# design.net
KiCad netlist of a schematic drawn in Altium Designer
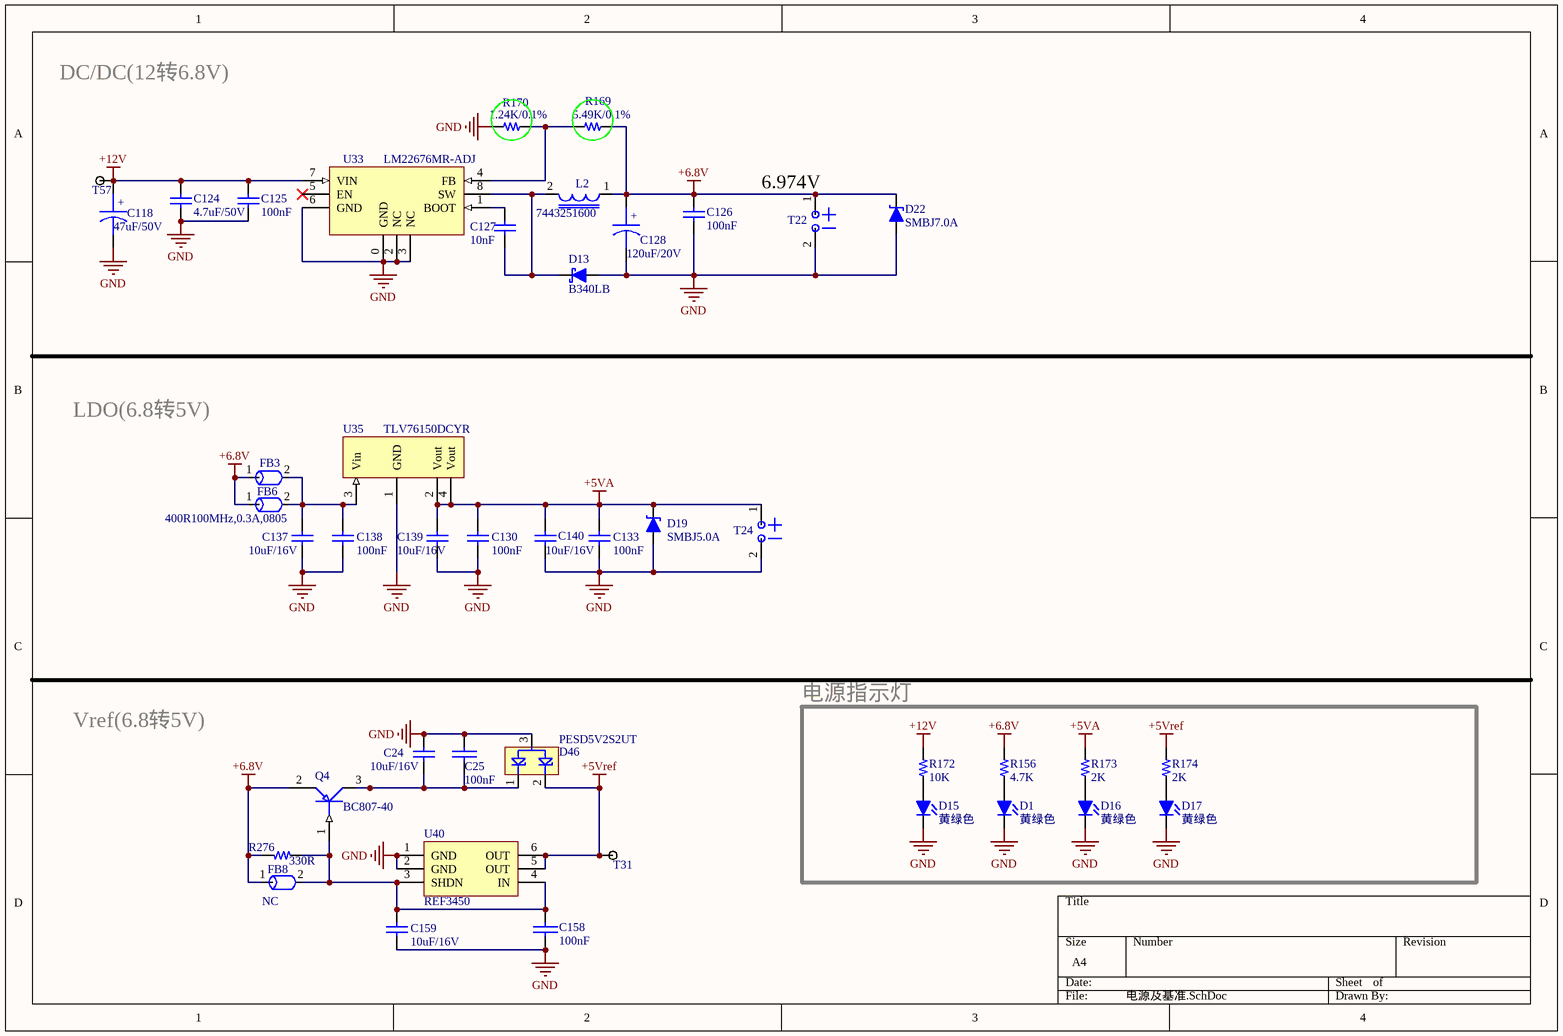
[diagram p0: 电源及基准.SchDoc]

(export (version "E")
  (design (tool "Eeschema 10.0.6"))
  (components
    (comp (ref "C24")
      (value "10uF/16V")
      (footprint "C-0805")
      (description "贴片瓷介电容100nF±5%,0805")
      (libsource (lib "电容") (part "100nF_1"))
    )
    (comp (ref "C25")
      (value "100nF")
      (footprint "C-0603")
      (description "Capacitor")
      (libsource (lib "*") (part "CAP"))
    )
    (comp (ref "C118")
      (value "47uF/50V")
      (footprint "CAP-SMD-φ6.3")
      (description "EEEFT1H470AP")
      (libsource (lib "电容") (part "10uF/16V贴片铝电解"))
    )
    (comp (ref "C124")
      (value "4.7uF/50V")
      (footprint "C-1210")
      (description "贴片瓷介电容100nF±5%,0805")
      (libsource (lib "电容") (part "100nF_1"))
    )
    (comp (ref "C125")
      (value "100nF")
      (footprint "C-0603")
      (description "贴片瓷介电容100nF±5%,0805")
      (libsource (lib "电容") (part "100nF_1"))
    )
    (comp (ref "C126")
      (value "100nF")
      (footprint "C-0603")
      (description "贴片瓷介电容100nF±5%,0805")
      (libsource (lib "电容") (part "100nF_1"))
    )
    (comp (ref "C127")
      (value "10nF")
      (footprint "C-0603")
      (description "贴片瓷介电容10nF±10%,0805")
      (libsource (lib "电容") (part "10nF_1"))
    )
    (comp (ref "C128")
      (value "120uF/20V")
      (footprint "CAP-SMD-φ6.3")
      (libsource (lib "电容") (part "100uF/25V贴片铝电解"))
    )
    (comp (ref "C130")
      (value "100nF")
      (footprint "C-0603")
      (description "贴片瓷介电容100nF±5%,0805")
      (libsource (lib "电容") (part "100nF_1"))
    )
    (comp (ref "C133")
      (value "100nF")
      (footprint "C-0603")
      (description "贴片瓷介电容100nF±5%,0805")
      (libsource (lib "电容") (part "100nF_1"))
    )
    (comp (ref "C137") (value "10uF/16V") (footprint "C-0805") (libsource (lib "Device") (part "C-1210")))
    (comp (ref "C138")
      (value "100nF")
      (footprint "C-0603")
      (description "贴片瓷介电容100nF±5%,0805")
      (libsource (lib "电容") (part "100nF_1"))
    )
    (comp (ref "C139") (value "10uF/16V") (footprint "C-0805") (libsource (lib "Device") (part "C-1210")))
    (comp (ref "C140") (value "10uF/16V") (footprint "C-0805") (libsource (lib "Device") (part "C-1210")))
    (comp (ref "C158")
      (value "100nF")
      (footprint "C-0603")
      (description "Capacitor")
      (libsource (lib "*") (part "CAP"))
    )
    (comp (ref "C159")
      (value "10uF/16V")
      (footprint "C-0805")
      (description "贴片瓷介电容100nF±5%,0805")
      (libsource (lib "电容") (part "100nF_1"))
    )
    (comp (ref "D1") (value "黄绿色") (footprint "LED-0805") (libsource (lib "Device") (part "LED-0805")))
    (comp (ref "D13")
      (value "B340LB")
      (footprint "DO-214AA/SMB")
      (libsource (lib "Device") (part "Diode-肖特基-214AA  (SMB)"))
    )
    (comp (ref "D15") (value "黄绿色") (footprint "LED-0805") (libsource (lib "Device") (part "LED-0805")))
    (comp (ref "D16") (value "黄绿色") (footprint "LED-0805") (libsource (lib "Device") (part "LED-0805")))
    (comp (ref "D17") (value "黄绿色") (footprint "LED-0805") (libsource (lib "Device") (part "LED-0805")))
    (comp (ref "D19")
      (value "SMBJ5.0A")
      (footprint "DO-214AA/SMB")
      (libsource (lib "Device") (part "Diode-稳压-213AB/LL34/MiniMELF"))
    )
    (comp (ref "D22")
      (value "SMBJ7.0A")
      (footprint "DO-214AA/SMB")
      (libsource (lib "Device") (part "Diode-稳压-213AB/LL34/MiniMELF"))
    )
    (comp (ref "D46") (value "PESD5V2S2UT") (footprint "sot23-3") (libsource (lib "IC") (part "PESDxS2UT")))
    (comp (ref "FB3")
      (value "400R100MHz,0.3A,0805")
      (footprint "R-0805")
      (description "Rdc0.3Ω,伍尔特,742792032")
      (libsource (lib "其它") (part "FB_1K/500mA_0805"))
    )
    (comp (ref "FB6")
      (value "400R100MHz,0.3A,0805")
      (footprint "R-0805")
      (description "Rdc0.3Ω,伍尔特,742792032")
      (libsource (lib "其它") (part "FB_1K/500mA_0805"))
    )
    (comp (ref "FB8")
      (value "NC")
      (footprint "R-0805")
      (description "Rdc0.3Ω,伍尔特,742792032")
      (libsource (lib "其它") (part "FB_1K/500mA_0805"))
    )
    (comp (ref "L2")
      (value "7443251600")
      (footprint "L-7050-WE-HCI")
      (libsource (lib "NBP电源板封装") (part "GPSR0750-220M"))
    )
    (comp (ref "Q4") (value "BC807-40") (footprint "SOT23-3") (libsource (lib "NBP电源板封装") (part "BC807-40")))
    (comp (ref "R156")
      (value "4.7K")
      (footprint "R-0603")
      (description "国巨RC0805FR-0710K")
      (libsource (lib "电阻") (part "10K_1"))
    )
    (comp (ref "R169")
      (value "5.49K/0.1%")
      (footprint "R-0603")
      (description "国巨RC0805FR-0710K")
      (libsource (lib "电阻") (part "10K_1"))
    )
    (comp (ref "R170")
      (value "1.24K/0.1%")
      (footprint "R-0603")
      (description "国巨RC0805FR-073K3")
      (libsource (lib "电阻") (part "3.3K_1"))
    )
    (comp (ref "R172")
      (value "10K")
      (footprint "R-0603")
      (description "国巨RC0805FR-0710K")
      (libsource (lib "电阻") (part "10K_1"))
    )
    (comp (ref "R173")
      (value "2K")
      (footprint "R-0603")
      (description "国巨RC0805FR-0710K")
      (libsource (lib "电阻") (part "10K_1"))
    )
    (comp (ref "R174")
      (value "2K")
      (footprint "R-0603")
      (description "国巨RC0805FR-0710K")
      (libsource (lib "电阻") (part "10K_1"))
    )
    (comp (ref "R276")
      (value "330R")
      (footprint "R-0805")
      (description "国巨RC0805FR-07100R")
      (libsource (lib "电阻") (part "100Ω_1"))
    )
    (comp (ref "T22") (value "POWER_TEST") (footprint "BT") (libsource (lib "其它") (part "POWER_TEST")))
    (comp (ref "T24") (value "POWER_TEST") (footprint "BT") (libsource (lib "其它") (part "POWER_TEST")))
    (comp (ref "T31") (value "直插测试点") (footprint "DIPTP") (libsource (lib "其它") (part "Testpiont")))
    (comp (ref "T57") (value "直插测试点") (footprint "DIPTP") (libsource (lib "其它") (part "Testpiont")))
    (comp (ref "U33")
      (value "LM22676MR-ADJ")
      (footprint "SOIC-8(4.90*3.9)-EPAD")
      (libsource (lib "IC") (part "LM22676MR-ADJ"))
    )
    (comp (ref "U35")
      (value "TLV76150DCYR")
      (footprint "IC:SOT223")
      (description "品牌：TI，型号：LM1117IMP-3.3/NOPB，800-mA Low-Dropout，SOT223，-40~+ 125°C，ROHS")
      (libsource (lib "IC") (part "LM1117IMP-3.3/NOPB"))
    )
    (comp (ref "U40") (value "REF3450") (footprint "SOT23-6") (libsource (lib "*") (part "REF3225")))
  )
  (nets
    (net (code "1") (name "+5VA") (class "Default")
      (node (ref "C130") (pin "2") (pinfunction "2_2") (pintype "passive"))
      (node (ref "C133") (pin "2") (pinfunction "2_2") (pintype "passive"))
      (node (ref "C139") (pin "2") (pinfunction "2_2") (pintype "passive"))
      (node (ref "C140") (pin "2") (pinfunction "2_2") (pintype "passive"))
      (node (ref "D19") (pin "K") (pinfunction "K_K") (pintype "passive"))
      (node (ref "R173") (pin "2") (pinfunction "BOT_2") (pintype "passive"))
      (node (ref "T24") (pin "1") (pinfunction "+_1") (pintype "passive"))
      (node (ref "U35") (pin "2") (pinfunction "Vout_2") (pintype "passive"))
      (node (ref "U35") (pin "4") (pinfunction "Vout_4") (pintype "passive"))
    )
    (net (code "2") (name "+5Vref") (class "Default")
      (node (ref "D46") (pin "2") (pinfunction "2_2") (pintype "passive"))
      (node (ref "R174") (pin "2") (pinfunction "BOT_2") (pintype "passive"))
      (node (ref "T31") (pin "1") (pinfunction "1_1") (pintype "passive"))
      (node (ref "U40") (pin "5") (pinfunction "OUT_5") (pintype "passive"))
      (node (ref "U40") (pin "6") (pinfunction "OUT_6") (pintype "passive"))
    )
    (net (code "3") (name "+6.8V") (class "Default")
      (node (ref "C126") (pin "2") (pinfunction "2_2") (pintype "passive"))
      (node (ref "C128") (pin "1") (pinfunction "1_1") (pintype "passive"))
      (node (ref "D22") (pin "K") (pinfunction "K_K") (pintype "passive"))
      (node (ref "FB3") (pin "1") (pinfunction "1_1") (pintype "passive"))
      (node (ref "FB6") (pin "1") (pinfunction "1_1") (pintype "passive"))
      (node (ref "FB8") (pin "1") (pinfunction "1_1") (pintype "passive"))
      (node (ref "L2") (pin "1") (pinfunction "1_1") (pintype "passive"))
      (node (ref "Q4") (pin "2") (pinfunction "E_2") (pintype "passive"))
      (node (ref "R156") (pin "2") (pinfunction "BOT_2") (pintype "passive"))
      (node (ref "R169") (pin "1") (pinfunction "TOP_1") (pintype "passive"))
      (node (ref "R276") (pin "2") (pinfunction "BOT_2") (pintype "passive"))
      (node (ref "T22") (pin "1") (pinfunction "+_1") (pintype "passive"))
    )
    (net (code "4") (name "+12V") (class "Default")
      (node (ref "C118") (pin "1") (pinfunction "1_1") (pintype "passive"))
      (node (ref "C124") (pin "2") (pinfunction "2_2") (pintype "passive"))
      (node (ref "C125") (pin "2") (pinfunction "2_2") (pintype "passive"))
      (node (ref "R172") (pin "2") (pinfunction "BOT_2") (pintype "passive"))
      (node (ref "T57") (pin "1") (pinfunction "1_1") (pintype "passive"))
      (node (ref "U33") (pin "7") (pinfunction "VIN_7") (pintype "input"))
    )
    (net (code "5") (name "GND") (class "Default")
      (node (ref "C118") (pin "2") (pinfunction "2_2") (pintype "passive"))
      (node (ref "C124") (pin "1") (pinfunction "1_1") (pintype "passive"))
      (node (ref "C125") (pin "1") (pinfunction "1_1") (pintype "passive"))
      (node (ref "C126") (pin "1") (pinfunction "1_1") (pintype "passive"))
      (node (ref "C128") (pin "2") (pinfunction "2_2") (pintype "passive"))
      (node (ref "C130") (pin "1") (pinfunction "1_1") (pintype "passive"))
      (node (ref "C133") (pin "1") (pinfunction "1_1") (pintype "passive"))
      (node (ref "C137") (pin "1") (pinfunction "1_1") (pintype "passive"))
      (node (ref "C138") (pin "1") (pinfunction "1_1") (pintype "passive"))
      (node (ref "C139") (pin "1") (pinfunction "1_1") (pintype "passive"))
      (node (ref "C140") (pin "1") (pinfunction "1_1") (pintype "passive"))
      (node (ref "C158") (pin "1") (pinfunction "1_1") (pintype "passive"))
      (node (ref "C159") (pin "1") (pinfunction "1_1") (pintype "passive"))
      (node (ref "C24") (pin "2") (pinfunction "2_2") (pintype "passive"))
      (node (ref "C25") (pin "2") (pinfunction "2_2") (pintype "passive"))
      (node (ref "D1") (pin "K") (pinfunction "K_K") (pintype "passive"))
      (node (ref "D13") (pin "A") (pinfunction "A_A") (pintype "passive"))
      (node (ref "D15") (pin "K") (pinfunction "K_K") (pintype "passive"))
      (node (ref "D16") (pin "K") (pinfunction "K_K") (pintype "passive"))
      (node (ref "D17") (pin "K") (pinfunction "K_K") (pintype "passive"))
      (node (ref "D19") (pin "A") (pinfunction "A_A") (pintype "passive"))
      (node (ref "D22") (pin "A") (pinfunction "A_A") (pintype "passive"))
      (node (ref "D46") (pin "3") (pinfunction "3_3") (pintype "passive"))
      (node (ref "R170") (pin "1") (pinfunction "TOP_1") (pintype "passive"))
      (node (ref "T22") (pin "2") (pinfunction "-_2") (pintype "passive"))
      (node (ref "T24") (pin "2") (pinfunction "-_2") (pintype "passive"))
      (node (ref "U33") (pin "0") (pinfunction "GND_0") (pintype "power_in"))
      (node (ref "U33") (pin "2") (pinfunction "NC_2") (pintype "passive"))
      (node (ref "U33") (pin "3") (pinfunction "NC_3") (pintype "passive"))
      (node (ref "U33") (pin "6") (pinfunction "GND_6") (pintype "power_in"))
      (node (ref "U35") (pin "1") (pinfunction "GND_1") (pintype "power_in"))
      (node (ref "U40") (pin "1") (pinfunction "GND_1") (pintype "passive"))
      (node (ref "U40") (pin "2") (pinfunction "GND_2") (pintype "passive"))
    )
    (net (code "6") (name "Net-(Q4-B)") (class "Default")
      (node (ref "C158") (pin "2") (pinfunction "2_2") (pintype "passive"))
      (node (ref "C159") (pin "2") (pinfunction "2_2") (pintype "passive"))
      (node (ref "FB8") (pin "2") (pinfunction "2_2") (pintype "passive"))
      (node (ref "Q4") (pin "1") (pinfunction "B_1") (pintype "input"))
      (node (ref "R276") (pin "1") (pinfunction "TOP_1") (pintype "passive"))
      (node (ref "U40") (pin "3") (pinfunction "SHDN_3") (pintype "passive"))
      (node (ref "U40") (pin "4") (pinfunction "IN_4") (pintype "passive"))
    )
    (net (code "7") (name "Net-(Q4-C)") (class "Default")
      (node (ref "C24") (pin "1") (pinfunction "1_1") (pintype "passive"))
      (node (ref "C25") (pin "1") (pinfunction "1_1") (pintype "passive"))
      (node (ref "D46") (pin "1") (pinfunction "1_1") (pintype "passive"))
      (node (ref "Q4") (pin "3") (pinfunction "C_3") (pintype "passive"))
    )
    (net (code "8") (name "Net-(R156-TOP)") (class "Default")
      (node (ref "D1") (pin "A") (pinfunction "A_A") (pintype "passive"))
      (node (ref "R156") (pin "1") (pinfunction "TOP_1") (pintype "passive"))
    )
    (net (code "9") (name "Net-(R169-BOT)") (class "Default")
      (node (ref "R169") (pin "2") (pinfunction "BOT_2") (pintype "passive"))
      (node (ref "R170") (pin "2") (pinfunction "BOT_2") (pintype "passive"))
      (node (ref "U33") (pin "4") (pinfunction "FB_4") (pintype "input"))
    )
    (net (code "10") (name "Net-(R172-TOP)") (class "Default")
      (node (ref "D15") (pin "A") (pinfunction "A_A") (pintype "passive"))
      (node (ref "R172") (pin "1") (pinfunction "TOP_1") (pintype "passive"))
    )
    (net (code "11") (name "Net-(R173-TOP)") (class "Default")
      (node (ref "D16") (pin "A") (pinfunction "A_A") (pintype "passive"))
      (node (ref "R173") (pin "1") (pinfunction "TOP_1") (pintype "passive"))
    )
    (net (code "12") (name "Net-(R174-TOP)") (class "Default")
      (node (ref "D17") (pin "A") (pinfunction "A_A") (pintype "passive"))
      (node (ref "R174") (pin "1") (pinfunction "TOP_1") (pintype "passive"))
    )
    (net (code "13") (name "Net-(U33-BOOT)") (class "Default")
      (node (ref "C127") (pin "2") (pinfunction "2_2") (pintype "passive"))
      (node (ref "U33") (pin "1") (pinfunction "BOOT_1") (pintype "input"))
    )
    (net (code "14") (name "Net-(U33-SW)") (class "Default")
      (node (ref "C127") (pin "1") (pinfunction "1_1") (pintype "passive"))
      (node (ref "D13") (pin "K") (pinfunction "K_K") (pintype "passive"))
      (node (ref "L2") (pin "2") (pinfunction "2_2") (pintype "passive"))
      (node (ref "U33") (pin "8") (pinfunction "SW_8") (pintype "passive"))
    )
    (net (code "15") (name "Net-(U35-Vin)") (class "Default")
      (node (ref "C137") (pin "2") (pinfunction "2_2") (pintype "passive"))
      (node (ref "C138") (pin "2") (pinfunction "2_2") (pintype "passive"))
      (node (ref "FB3") (pin "2") (pinfunction "2_2") (pintype "passive"))
      (node (ref "FB6") (pin "2") (pinfunction "2_2") (pintype "passive"))
      (node (ref "U35") (pin "3") (pinfunction "Vin_3") (pintype "input"))
    )
    (net (code "16") (name "unconnected-(U33-EN-Pad5)") (class "Default")
      (node (ref "U33") (pin "5") (pinfunction "EN_5") (pintype "passive+no_connect"))
    )
  )
)
